# Tachometer_v1_0.net
KiCad netlist of a schematic drawn in EAGLE
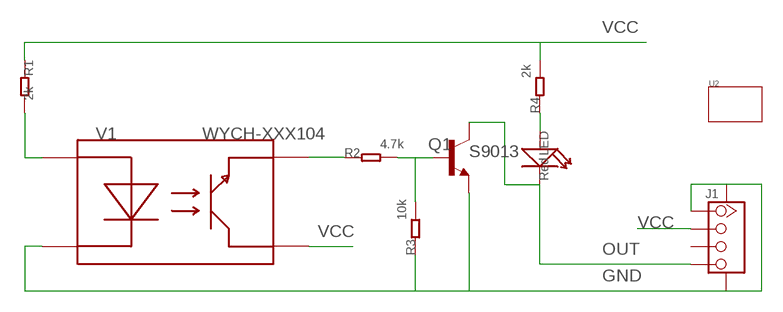
[diagram p0: schematic, sheet 1]

(export (version "E")
  (design (tool "Eeschema 10.0.6"))
  (components
    (comp (ref "J1")
      (value "TWIG-4P-2.0-SMD-FEMALE-REINFORCE'DD'")
      (footprint "eagle-import:4P-SMD-2.0")
      (libsource (lib "eagle-import") (part "TWIG-4P-2.0-SMD-FEMALE-REINFORCE'DD'"))
    )
    (comp (ref "LED")
      (value "Red")
      (footprint "eagle-import:LED-0603")
      (libsource (lib "eagle-import") (part "LED'0603'"))
    )
    (comp (ref "Q1")
      (value "S9013")
      (footprint "eagle-import:SOT23-3")
      (libsource (lib "eagle-import") (part "TRANSISTOR_NPNSOT23-3"))
    )
    (comp (ref "R1")
      (value "2k")
      (footprint "eagle-import:R0603")
      (libsource (lib "eagle-import") (part "R-0603"))
    )
    (comp (ref "R2")
      (value "4.7k")
      (footprint "eagle-import:R0603")
      (libsource (lib "eagle-import") (part "R-0603"))
    )
    (comp (ref "R3")
      (value "10k")
      (footprint "eagle-import:R0603")
      (libsource (lib "eagle-import") (part "R-0603"))
    )
    (comp (ref "R4")
      (value "2k")
      (footprint "eagle-import:R0603")
      (libsource (lib "eagle-import") (part "R-0603"))
    )
    (comp (ref "U2")
      (value "TWIG-2U")
      (footprint "eagle-import:2U-DIM-W_-DRILL")
      (libsource (lib "eagle-import") (part "TWIG-2U"))
    )
    (comp (ref "V1")
      (value "WYCH-XXX104")
      (footprint "eagle-import:WYCH104")
      (libsource (lib "eagle-import") (part "WYCH-XXX104"))
    )
  )
  (nets
    (net (code "1") (name "/GND") (class "Default")
      (node (ref "J1") (pin "1") (pinfunction "1_1") (pintype "bidirectional"))
      (node (ref "J1") (pin "SS1") (pinfunction "SS1_SS1") (pintype "bidirectional"))
      (node (ref "J1") (pin "SS2") (pinfunction "SS2_SS2") (pintype "bidirectional"))
      (node (ref "Q1") (pin "2") (pinfunction "E_2") (pintype "passive"))
      (node (ref "R3") (pin "1") (pinfunction "1_1") (pintype "passive"))
      (node (ref "V1") (pin "2") (pinfunction "2_2") (pintype "bidirectional"))
    )
    (net (code "2") (name "/OUT") (class "Default")
      (node (ref "J1") (pin "4") (pinfunction "4_4") (pintype "bidirectional"))
      (node (ref "LED") (pin "-") (pinfunction "-_-") (pintype "passive"))
      (node (ref "Q1") (pin "3") (pinfunction "C_3") (pintype "passive"))
    )
    (net (code "3") (name "/VCC") (class "Default")
      (node (ref "J1") (pin "2") (pinfunction "2_2") (pintype "bidirectional"))
      (node (ref "R1") (pin "1") (pinfunction "1_1") (pintype "passive"))
      (node (ref "R4") (pin "2") (pinfunction "2_2") (pintype "passive"))
      (node (ref "V1") (pin "3") (pinfunction "3_3") (pintype "bidirectional"))
    )
    (net (code "4") (name "Net-(LED-Pad+)") (class "Default")
      (node (ref "LED") (pin "+") (pinfunction "+_+") (pintype "passive"))
      (node (ref "R4") (pin "1") (pinfunction "1_1") (pintype "passive"))
    )
    (net (code "5") (name "Net-(Q1-B)") (class "Default")
      (node (ref "Q1") (pin "1") (pinfunction "B_1") (pintype "passive"))
      (node (ref "R2") (pin "2") (pinfunction "2_2") (pintype "passive"))
      (node (ref "R3") (pin "2") (pinfunction "2_2") (pintype "passive"))
    )
    (net (code "6") (name "Net-(R1-Pad2)") (class "Default")
      (node (ref "R1") (pin "2") (pinfunction "2_2") (pintype "passive"))
      (node (ref "V1") (pin "1") (pinfunction "1_1") (pintype "bidirectional"))
    )
    (net (code "7") (name "Net-(R2-Pad1)") (class "Default")
      (node (ref "R2") (pin "1") (pinfunction "1_1") (pintype "passive"))
      (node (ref "V1") (pin "4") (pinfunction "4_4") (pintype "bidirectional"))
    )
    (net (code "8") (name "unconnected-(J1-Pad3)") (class "Default")
      (node (ref "J1") (pin "3") (pinfunction "3_3") (pintype "bidirectional"))
    )
  )
)
